# laser_optocoupler_rev00.net
KiCad netlist of a schematic drawn in EAGLE
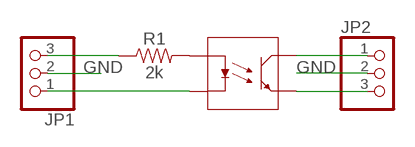
[diagram p0: schematic, sheet 1]

(export (version "E")
  (design (tool "Eeschema 10.0.6"))
  (components
    (comp (ref "JP1")
      (value "PINHD-1X3")
      (footprint "eagle-import:1X03")
      (libsource (lib "eagle-import") (part "PINHD-1X3"))
    )
    (comp (ref "JP2")
      (value "PINHD-1X3")
      (footprint "eagle-import:1X03")
      (libsource (lib "eagle-import") (part "PINHD-1X3"))
    )
    (comp (ref "R1")
      (value "2k")
      (footprint "eagle-import:0603")
      (libsource (lib "eagle-import") (part "1.8MOHM"))
    )
    (comp (ref "U$1")
      (value "PS2701")
      (footprint "eagle-import:SOP_4PIN")
      (libsource (lib "eagle-import") (part "PS2701"))
    )
  )
  (nets
    (net (code "1") (name "/GND") (class "Default")
      (node (ref "JP1") (pin "2") (pinfunction "2_2") (pintype "passive"))
      (node (ref "JP2") (pin "2") (pinfunction "2_2") (pintype "passive"))
    )
    (net (code "2") (name "Net-(JP1-Pad1)") (class "Default")
      (node (ref "JP1") (pin "1") (pinfunction "1_1") (pintype "passive"))
      (node (ref "U$1") (pin "2") (pinfunction "2_2") (pintype "bidirectional"))
    )
    (net (code "3") (name "Net-(JP1-Pad3)") (class "Default")
      (node (ref "JP1") (pin "3") (pinfunction "3_3") (pintype "passive"))
      (node (ref "R1") (pin "1") (pinfunction "1_1") (pintype "passive"))
    )
    (net (code "4") (name "Net-(JP2-Pad1)") (class "Default")
      (node (ref "JP2") (pin "1") (pinfunction "1_1") (pintype "passive"))
      (node (ref "U$1") (pin "4") (pinfunction "4_4") (pintype "bidirectional"))
    )
    (net (code "5") (name "Net-(JP2-Pad3)") (class "Default")
      (node (ref "JP2") (pin "3") (pinfunction "3_3") (pintype "passive"))
      (node (ref "U$1") (pin "3") (pinfunction "3_3") (pintype "bidirectional"))
    )
    (net (code "6") (name "Net-(R1-Pad2)") (class "Default")
      (node (ref "R1") (pin "2") (pinfunction "2_2") (pintype "passive"))
      (node (ref "U$1") (pin "1") (pinfunction "1_1") (pintype "bidirectional"))
    )
  )
)
